# Ethernet.net
KiCad netlist of a schematic drawn in Altium Designer
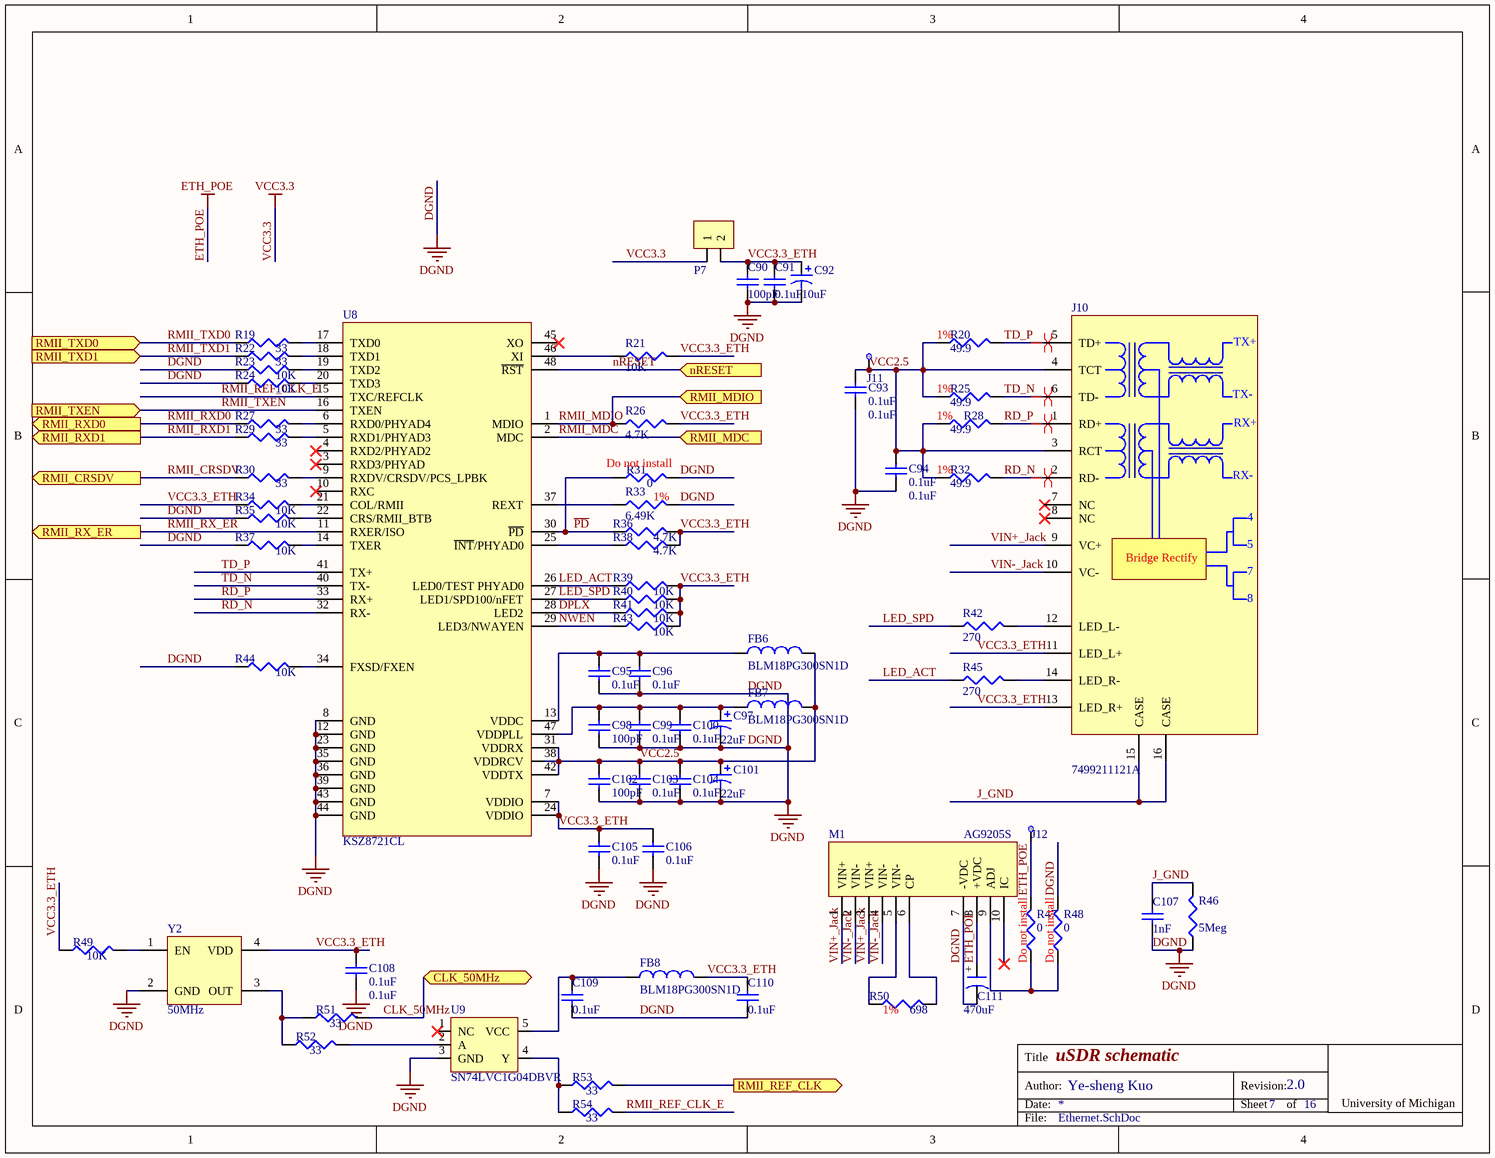
[diagram p0: Ethernet.SchDoc]

(export (version "E")
  (design (tool "Eeschema 10.0.6"))
  (components
    (comp (ref "C90")
      (value "100pF")
      (footprint "0402")
      (description "Capacitor (Semiconductor SIM Model)")
      (fields (field (name "PUBLISHER") "Altium Limited"))
      (libsource (lib "Miscellaneous Devices") (part "Cap Semi"))
    )
    (comp (ref "C91")
      (value "0.1uF")
      (footprint "0402")
      (description "Capacitor (Semiconductor SIM Model)")
      (fields (field (name "PUBLISHER") "Altium Limited"))
      (libsource (lib "Miscellaneous Devices") (part "Cap Semi"))
    )
    (comp (ref "C92")
      (value "10uF")
      (footprint "C0805")
      (description "Polarized Capacitor (Surface Mount)")
      (fields (field (name "PUBLISHER") "Altium Limited"))
      (libsource (lib "Miscellaneous Devices") (part "Cap Pol3"))
    )
    (comp (ref "C93")
      (value "0.1uF")
      (footprint "0402")
      (description "Capacitor (Semiconductor SIM Model)")
      (fields (field (name "ALTIUM_VALUE") "0.1uF") (field (name "PUBLISHER") "Altium Limited"))
      (libsource (lib "Miscellaneous Devices") (part "Cap Semi"))
    )
    (comp (ref "C94")
      (value "0.1uF")
      (footprint "0402")
      (description "Capacitor (Semiconductor SIM Model)")
      (fields (field (name "ALTIUM_VALUE") "0.1uF") (field (name "PUBLISHER") "Altium Limited"))
      (libsource (lib "Miscellaneous Devices") (part "Cap Semi"))
    )
    (comp (ref "C95")
      (value "0.1uF")
      (footprint "0402")
      (description "Capacitor (Semiconductor SIM Model)")
      (fields (field (name "PUBLISHER") "Altium Limited"))
      (libsource (lib "Miscellaneous Devices") (part "Cap Semi"))
    )
    (comp (ref "C96")
      (value "0.1uF")
      (footprint "0402")
      (description "Capacitor (Semiconductor SIM Model)")
      (fields (field (name "PUBLISHER") "Altium Limited"))
      (libsource (lib "Miscellaneous Devices") (part "Cap Semi"))
    )
    (comp (ref "C97")
      (value "22uF")
      (footprint "C0805")
      (description "Polarized Capacitor (Surface Mount)")
      (fields (field (name "PUBLISHER") "Altium Limited"))
      (libsource (lib "Miscellaneous Devices") (part "Cap Pol3"))
    )
    (comp (ref "C98")
      (value "100pF")
      (footprint "0402")
      (description "Capacitor (Semiconductor SIM Model)")
      (fields (field (name "PUBLISHER") "Altium Limited"))
      (libsource (lib "Miscellaneous Devices") (part "Cap Semi"))
    )
    (comp (ref "C99")
      (value "0.1uF")
      (footprint "0402")
      (description "Capacitor (Semiconductor SIM Model)")
      (fields (field (name "PUBLISHER") "Altium Limited"))
      (libsource (lib "Miscellaneous Devices") (part "Cap Semi"))
    )
    (comp (ref "C100")
      (value "0.1uF")
      (footprint "0402")
      (description "Capacitor (Semiconductor SIM Model)")
      (fields (field (name "PUBLISHER") "Altium Limited"))
      (libsource (lib "Miscellaneous Devices") (part "Cap Semi"))
    )
    (comp (ref "C101")
      (value "22uF")
      (footprint "C0805")
      (description "Polarized Capacitor (Surface Mount)")
      (fields (field (name "PUBLISHER") "Altium Limited"))
      (libsource (lib "Miscellaneous Devices") (part "Cap Pol3"))
    )
    (comp (ref "C102")
      (value "100pF")
      (footprint "0402")
      (description "Capacitor (Semiconductor SIM Model)")
      (fields (field (name "PUBLISHER") "Altium Limited"))
      (libsource (lib "Miscellaneous Devices") (part "Cap Semi"))
    )
    (comp (ref "C103")
      (value "0.1uF")
      (footprint "0402")
      (description "Capacitor (Semiconductor SIM Model)")
      (fields (field (name "PUBLISHER") "Altium Limited"))
      (libsource (lib "Miscellaneous Devices") (part "Cap Semi"))
    )
    (comp (ref "C104")
      (value "0.1uF")
      (footprint "0402")
      (description "Capacitor (Semiconductor SIM Model)")
      (fields (field (name "PUBLISHER") "Altium Limited"))
      (libsource (lib "Miscellaneous Devices") (part "Cap Semi"))
    )
    (comp (ref "C105")
      (value "0.1uF")
      (footprint "0402")
      (description "Capacitor (Semiconductor SIM Model)")
      (fields (field (name "PUBLISHER") "Altium Limited"))
      (libsource (lib "Miscellaneous Devices") (part "Cap Semi"))
    )
    (comp (ref "C106")
      (value "0.1uF")
      (footprint "0402")
      (description "Capacitor (Semiconductor SIM Model)")
      (fields (field (name "PUBLISHER") "Altium Limited"))
      (libsource (lib "Miscellaneous Devices") (part "Cap Semi"))
    )
    (comp (ref "C107")
      (value "1nF")
      (footprint "0402")
      (description "Capacitor (Semiconductor SIM Model)")
      (fields (field (name "PUBLISHER") "Altium Limited"))
      (libsource (lib "Miscellaneous Devices") (part "Cap Semi"))
    )
    (comp (ref "C108")
      (value "0.1uF")
      (footprint "0402")
      (description "Capacitor (Semiconductor SIM Model)")
      (fields (field (name "ALTIUM_VALUE") "0.1uF") (field (name "PUBLISHER") "Altium Limited"))
      (libsource (lib "Miscellaneous Devices") (part "Cap Semi"))
    )
    (comp (ref "C109")
      (value "0.1uF")
      (footprint "0402")
      (description "Capacitor (Semiconductor SIM Model)")
      (fields (field (name "PUBLISHER") "Altium Limited"))
      (libsource (lib "Miscellaneous Devices") (part "Cap Semi"))
    )
    (comp (ref "C110")
      (value "0.1uF")
      (footprint "0402")
      (description "Capacitor (Semiconductor SIM Model)")
      (fields (field (name "PUBLISHER") "Altium Limited"))
      (libsource (lib "Miscellaneous Devices") (part "Cap Semi"))
    )
    (comp (ref "C111") (value "470uF") (footprint "SMT Al Cap.") (libsource (lib "SDR") (part "Cap")))
    (comp (ref "FB6")
      (value "BLM18PG300SN1D")
      (footprint "1608[0603]")
      (description "FERRITE CHIP 30 OHM 1000MA 0603")
      (libsource (lib "SDR") (part "Ferrite Bead"))
    )
    (comp (ref "FB7")
      (value "BLM18PG300SN1D")
      (footprint "1608[0603]")
      (description "FERRITE CHIP 30 OHM 1000MA 0603")
      (libsource (lib "SDR") (part "Ferrite Bead"))
    )
    (comp (ref "FB8")
      (value "BLM18PG300SN1D")
      (footprint "1608[0603]")
      (description "FERRITE CHIP 30 OHM 1000MA 0603")
      (libsource (lib "SDR") (part "Ferrite Bead"))
    )
    (comp (ref "J10")
      (value "7499211121A")
      (footprint "7499211121A")
      (description "CONN RJ45 8-8 W/TRANSFORMER")
      (libsource (lib "SDR") (part "Ethernet Jack PoE"))
    )
    (comp (ref "J11")
      (value "5004")
      (footprint "TestPoint")
      (description "TEST POINT PC MINI .040\"D YELLOW")
      (libsource (lib "SDR") (part "TestPoint"))
    )
    (comp (ref "J12")
      (value "5004")
      (footprint "TestPoint")
      (description "TEST POINT PC MINI .040\"D YELLOW")
      (libsource (lib "SDR") (part "TestPoint"))
    )
    (comp (ref "M1")
      (value "AG9205S")
      (footprint "AG9205S")
      (description "Silver Telecom AG9205S POE")
      (libsource (lib "SDR") (part "AG9205S"))
    )
    (comp (ref "P7")
      (value "1 x 2 header")
      (footprint "1x2 header")
      (description "100 mils standard header")
      (libsource (lib "SDR") (part "1 x 2 header"))
    )
    (comp (ref "R19")
      (value "33")
      (footprint "0402")
      (description "Resistor")
      (fields (field (name "PUBLISHER") "Altium Limited"))
      (libsource (lib "Miscellaneous Devices") (part "Res3"))
    )
    (comp (ref "R20")
      (value "49.9")
      (footprint "0402")
      (description "Resistor")
      (fields (field (name "PUBLISHER") "Altium Limited"))
      (libsource (lib "Miscellaneous Devices") (part "Res3"))
    )
    (comp (ref "R21")
      (value "10K")
      (footprint "0402")
      (description "Resistor")
      (fields (field (name "PUBLISHER") "Altium Limited"))
      (libsource (lib "Miscellaneous Devices") (part "Res3"))
    )
    (comp (ref "R22")
      (value "33")
      (footprint "0402")
      (description "Resistor")
      (fields (field (name "PUBLISHER") "Altium Limited"))
      (libsource (lib "Miscellaneous Devices") (part "Res3"))
    )
    (comp (ref "R23")
      (value "10K")
      (footprint "0402")
      (description "Resistor")
      (fields (field (name "PUBLISHER") "Altium Limited"))
      (libsource (lib "Miscellaneous Devices") (part "Res3"))
    )
    (comp (ref "R24")
      (value "10K")
      (footprint "0402")
      (description "Resistor")
      (fields (field (name "PUBLISHER") "Altium Limited"))
      (libsource (lib "Miscellaneous Devices") (part "Res3"))
    )
    (comp (ref "R25")
      (value "49.9")
      (footprint "0402")
      (description "Resistor")
      (fields (field (name "PUBLISHER") "Altium Limited"))
      (libsource (lib "Miscellaneous Devices") (part "Res3"))
    )
    (comp (ref "R26")
      (value "4.7K")
      (footprint "0402")
      (description "Resistor")
      (fields (field (name "PUBLISHER") "Altium Limited"))
      (libsource (lib "Miscellaneous Devices") (part "Res3"))
    )
    (comp (ref "R27")
      (value "33")
      (footprint "0402")
      (description "Resistor")
      (fields (field (name "PUBLISHER") "Altium Limited"))
      (libsource (lib "Miscellaneous Devices") (part "Res3"))
    )
    (comp (ref "R28")
      (value "49.9")
      (footprint "0402")
      (description "Resistor")
      (fields (field (name "PUBLISHER") "Altium Limited"))
      (libsource (lib "Miscellaneous Devices") (part "Res3"))
    )
    (comp (ref "R29")
      (value "33")
      (footprint "0402")
      (description "Resistor")
      (fields (field (name "PUBLISHER") "Altium Limited"))
      (libsource (lib "Miscellaneous Devices") (part "Res3"))
    )
    (comp (ref "R30")
      (value "33")
      (footprint "0402")
      (description "Resistor")
      (fields (field (name "PUBLISHER") "Altium Limited"))
      (libsource (lib "Miscellaneous Devices") (part "Res3"))
    )
    (comp (ref "R31")
      (value "0")
      (footprint "0402")
      (description "Resistor")
      (fields (field (name "PUBLISHER") "Altium Limited"))
      (libsource (lib "Miscellaneous Devices") (part "Res3"))
    )
    (comp (ref "R32")
      (value "49.9")
      (footprint "0402")
      (description "Resistor")
      (fields (field (name "PUBLISHER") "Altium Limited"))
      (libsource (lib "Miscellaneous Devices") (part "Res3"))
    )
    (comp (ref "R33")
      (value "6.49K")
      (footprint "0402")
      (description "Resistor")
      (fields (field (name "PUBLISHER") "Altium Limited"))
      (libsource (lib "Miscellaneous Devices") (part "Res3"))
    )
    (comp (ref "R34")
      (value "10K")
      (footprint "0402")
      (description "Resistor")
      (fields (field (name "PUBLISHER") "Altium Limited"))
      (libsource (lib "Miscellaneous Devices") (part "Res3"))
    )
    (comp (ref "R35")
      (value "10K")
      (footprint "0402")
      (description "Resistor")
      (fields (field (name "PUBLISHER") "Altium Limited"))
      (libsource (lib "Miscellaneous Devices") (part "Res3"))
    )
    (comp (ref "R36")
      (value "4.7K")
      (footprint "0402")
      (description "Resistor")
      (fields (field (name "PUBLISHER") "Altium Limited"))
      (libsource (lib "Miscellaneous Devices") (part "Res3"))
    )
    (comp (ref "R37")
      (value "10K")
      (footprint "0402")
      (description "Resistor")
      (fields (field (name "PUBLISHER") "Altium Limited"))
      (libsource (lib "Miscellaneous Devices") (part "Res3"))
    )
    (comp (ref "R38")
      (value "4.7K")
      (footprint "0402")
      (description "Resistor")
      (fields (field (name "PUBLISHER") "Altium Limited"))
      (libsource (lib "Miscellaneous Devices") (part "Res3"))
    )
    (comp (ref "R39")
      (value "10K")
      (footprint "0402")
      (description "Resistor")
      (fields (field (name "PUBLISHER") "Altium Limited"))
      (libsource (lib "Miscellaneous Devices") (part "Res3"))
    )
    (comp (ref "R40")
      (value "10K")
      (footprint "0402")
      (description "Resistor")
      (fields (field (name "PUBLISHER") "Altium Limited"))
      (libsource (lib "Miscellaneous Devices") (part "Res3"))
    )
    (comp (ref "R41")
      (value "10K")
      (footprint "0402")
      (description "Resistor")
      (fields (field (name "PUBLISHER") "Altium Limited"))
      (libsource (lib "Miscellaneous Devices") (part "Res3"))
    )
    (comp (ref "R42")
      (value "270")
      (footprint "0402")
      (description "Resistor")
      (fields (field (name "PUBLISHER") "Altium Limited"))
      (libsource (lib "Miscellaneous Devices") (part "Res3"))
    )
    (comp (ref "R43")
      (value "10K")
      (footprint "0402")
      (description "Resistor")
      (fields (field (name "PUBLISHER") "Altium Limited"))
      (libsource (lib "Miscellaneous Devices") (part "Res3"))
    )
    (comp (ref "R44")
      (value "10K")
      (footprint "0402")
      (description "Resistor")
      (fields (field (name "PUBLISHER") "Altium Limited"))
      (libsource (lib "Miscellaneous Devices") (part "Res3"))
    )
    (comp (ref "R45")
      (value "270")
      (footprint "0402")
      (description "Resistor")
      (fields (field (name "PUBLISHER") "Altium Limited"))
      (libsource (lib "Miscellaneous Devices") (part "Res3"))
    )
    (comp (ref "R46")
      (value "5Meg")
      (footprint "J1-0603")
      (description "Resistor")
      (fields (field (name "Comment") "5M") (field (name "PUBLISHER") "Altium Limited"))
      (libsource (lib "Miscellaneous Devices") (part "Res3"))
    )
    (comp (ref "R47")
      (value "0")
      (footprint "0402")
      (description "Resistor")
      (fields (field (name "PUBLISHER") "Altium Limited"))
      (libsource (lib "Miscellaneous Devices") (part "Res3"))
    )
    (comp (ref "R48")
      (value "0")
      (footprint "0402")
      (description "Resistor")
      (fields (field (name "PUBLISHER") "Altium Limited"))
      (libsource (lib "Miscellaneous Devices") (part "Res3"))
    )
    (comp (ref "R49")
      (value "10K")
      (footprint "0402")
      (description "Resistor")
      (fields (field (name "PUBLISHER") "Altium Limited"))
      (libsource (lib "Miscellaneous Devices") (part "Res3"))
    )
    (comp (ref "R50")
      (value "698")
      (footprint "0402")
      (description "Resistor")
      (fields (field (name "PUBLISHER") "Altium Limited"))
      (libsource (lib "Miscellaneous Devices") (part "Res3"))
    )
    (comp (ref "R51")
      (value "33")
      (footprint "0402")
      (description "Resistor")
      (fields (field (name "PUBLISHER") "Altium Limited"))
      (libsource (lib "Miscellaneous Devices") (part "Res3"))
    )
    (comp (ref "R52")
      (value "33")
      (footprint "0402")
      (description "Resistor")
      (fields (field (name "PUBLISHER") "Altium Limited"))
      (libsource (lib "Miscellaneous Devices") (part "Res3"))
    )
    (comp (ref "R53")
      (value "33")
      (footprint "0402")
      (description "Resistor")
      (fields (field (name "PUBLISHER") "Altium Limited"))
      (libsource (lib "Miscellaneous Devices") (part "Res3"))
    )
    (comp (ref "R54")
      (value "33")
      (footprint "0402")
      (description "Resistor")
      (fields (field (name "PUBLISHER") "Altium Limited"))
      (libsource (lib "Miscellaneous Devices") (part "Res3"))
    )
    (comp (ref "U8")
      (value "KSZ8721CL")
      (footprint "TSQFP50P900X900X160-48N")
      (description "IC TXRX PHY 10/100 3.3V 48-LQFP")
      (libsource (lib "SDR") (part "KSZ8721CL"))
    )
    (comp (ref "U9")
      (value "SN74LVC1G04DBVR")
      (footprint "SOT23-5")
      (description "IC SINGLE INVERTER-GATE SOT-23-5")
      (libsource (lib "SDR") (part "SN74LVC1G04DBV"))
    )
    (comp (ref "Y2")
      (value "50MHz")
      (footprint "CB3_CB3LV")
      (description "OSC 50.000 MHZ 3.3V SMD")
      (fields (field (name "Comment") "CB3LV-3C-50M0000"))
      (libsource (lib "SDR") (part "CB3_CB3LV"))
    )
  )
  (nets
    (net (code "1") (name "/CLK_50MHz") (class "Default")
      (node (ref "R51") (pin "2") (pinfunction "2_2") (pintype "passive"))
    )
    (net (code "2") (name "/DPLX") (class "Default")
      (node (ref "R41") (pin "1") (pinfunction "1_1") (pintype "passive"))
      (node (ref "U8") (pin "28") (pinfunction "LED2_28") (pintype "passive"))
    )
    (net (code "3") (name "/J_GND") (class "Default")
      (node (ref "C107") (pin "2") (pinfunction "2_2") (pintype "passive"))
      (node (ref "J10") (pin "15") (pinfunction "CASE_15") (pintype "passive"))
      (node (ref "J10") (pin "16") (pinfunction "CASE_16") (pintype "passive"))
      (node (ref "R46") (pin "2") (pinfunction "2_2") (pintype "passive"))
    )
    (net (code "4") (name "/LED_ACT") (class "Default")
      (node (ref "R39") (pin "1") (pinfunction "1_1") (pintype "passive"))
      (node (ref "R45") (pin "1") (pinfunction "1_1") (pintype "passive"))
      (node (ref "U8") (pin "26") (pinfunction "LED0/TEST_PHYAD0_26") (pintype "passive"))
    )
    (net (code "5") (name "/LED_SPD") (class "Default")
      (node (ref "R40") (pin "1") (pinfunction "1_1") (pintype "passive"))
      (node (ref "R42") (pin "1") (pinfunction "1_1") (pintype "passive"))
      (node (ref "U8") (pin "27") (pinfunction "LED1/SPD100/nFET_27") (pintype "passive"))
    )
    (net (code "6") (name "/NWEN") (class "Default")
      (node (ref "R43") (pin "1") (pinfunction "1_1") (pintype "passive"))
      (node (ref "U8") (pin "29") (pinfunction "LED3/NWAYEN_29") (pintype "passive"))
    )
    (net (code "7") (name "/RD_N") (class "Default")
      (node (ref "J10") (pin "2") (pinfunction "RD-_2") (pintype "passive"))
      (node (ref "R32") (pin "2") (pinfunction "2_2") (pintype "passive"))
      (node (ref "U8") (pin "32") (pinfunction "RX-_32") (pintype "passive"))
    )
    (net (code "8") (name "/RD_P") (class "Default")
      (node (ref "J10") (pin "1") (pinfunction "RD+_1") (pintype "passive"))
      (node (ref "R28") (pin "2") (pinfunction "2_2") (pintype "passive"))
      (node (ref "U8") (pin "33") (pinfunction "RX+_33") (pintype "passive"))
    )
    (net (code "9") (name "/RMII_CRSDV") (class "Default")
      (node (ref "R30") (pin "1") (pinfunction "1_1") (pintype "passive"))
    )
    (net (code "10") (name "/RMII_MDC") (class "Default")
      (node (ref "U8") (pin "2") (pinfunction "MDC_2") (pintype "passive"))
    )
    (net (code "11") (name "/RMII_MDIO") (class "Default")
      (node (ref "R26") (pin "1") (pinfunction "1_1") (pintype "passive"))
      (node (ref "U8") (pin "1") (pinfunction "MDIO_1") (pintype "passive"))
    )
    (net (code "12") (name "/RMII_REF_CLK") (class "Default")
      (node (ref "R53") (pin "2") (pinfunction "2_2") (pintype "passive"))
    )
    (net (code "13") (name "/RMII_REF_CLK_E") (class "Default")
      (node (ref "R54") (pin "2") (pinfunction "2_2") (pintype "passive"))
      (node (ref "U8") (pin "15") (pinfunction "TXC/REFCLK_15") (pintype "passive"))
    )
    (net (code "14") (name "/RMII_RXD0") (class "Default")
      (node (ref "R27") (pin "1") (pinfunction "1_1") (pintype "passive"))
    )
    (net (code "15") (name "/RMII_RXD1") (class "Default")
      (node (ref "R29") (pin "1") (pinfunction "1_1") (pintype "passive"))
    )
    (net (code "16") (name "/RMII_RX_ER") (class "Default")
      (node (ref "U8") (pin "11") (pinfunction "RXER/ISO_11") (pintype "passive"))
    )
    (net (code "17") (name "/RMII_TXD0") (class "Default")
      (node (ref "R19") (pin "1") (pinfunction "1_1") (pintype "passive"))
    )
    (net (code "18") (name "/RMII_TXD1") (class "Default")
      (node (ref "R22") (pin "1") (pinfunction "1_1") (pintype "passive"))
    )
    (net (code "19") (name "/RMII_TXEN") (class "Default")
      (node (ref "U8") (pin "16") (pinfunction "TXEN_16") (pintype "passive"))
    )
    (net (code "20") (name "/TD_N") (class "Default")
      (node (ref "J10") (pin "6") (pinfunction "TD-_6") (pintype "passive"))
      (node (ref "R25") (pin "2") (pinfunction "2_2") (pintype "passive"))
      (node (ref "U8") (pin "40") (pinfunction "TX-_40") (pintype "passive"))
    )
    (net (code "21") (name "/TD_P") (class "Default")
      (node (ref "J10") (pin "5") (pinfunction "TD+_5") (pintype "passive"))
      (node (ref "R20") (pin "2") (pinfunction "2_2") (pintype "passive"))
      (node (ref "U8") (pin "41") (pinfunction "TX+_41") (pintype "passive"))
    )
    (net (code "22") (name "/VCC2.5") (class "Default")
      (node (ref "C101") (pin "1") (pinfunction "1_1") (pintype "passive"))
      (node (ref "C102") (pin "2") (pinfunction "2_2") (pintype "passive"))
      (node (ref "C103") (pin "2") (pinfunction "2_2") (pintype "passive"))
      (node (ref "C104") (pin "2") (pinfunction "2_2") (pintype "passive"))
      (node (ref "C93") (pin "2") (pinfunction "2_2") (pintype "passive"))
      (node (ref "C94") (pin "2") (pinfunction "2_2") (pintype "passive"))
      (node (ref "FB6") (pin "2") (pinfunction "2_2") (pintype "passive"))
      (node (ref "FB7") (pin "2") (pinfunction "2_2") (pintype "passive"))
      (node (ref "J10") (pin "3") (pinfunction "RCT_3") (pintype "passive"))
      (node (ref "J10") (pin "4") (pinfunction "TCT_4") (pintype "passive"))
      (node (ref "J11") (pin "1") (pinfunction "TB_1") (pintype "passive"))
      (node (ref "R20") (pin "1") (pinfunction "1_1") (pintype "passive"))
      (node (ref "R25") (pin "1") (pinfunction "1_1") (pintype "passive"))
      (node (ref "R28") (pin "1") (pinfunction "1_1") (pintype "passive"))
      (node (ref "R32") (pin "1") (pinfunction "1_1") (pintype "passive"))
      (node (ref "U8") (pin "31") (pinfunction "VDDRX_31") (pintype "passive"))
      (node (ref "U8") (pin "38") (pinfunction "VDDRCV_38") (pintype "passive"))
      (node (ref "U8") (pin "42") (pinfunction "VDDTX_42") (pintype "passive"))
    )
    (net (code "23") (name "/VCC3.3_ETH") (class "Default")
      (node (ref "C105") (pin "2") (pinfunction "2_2") (pintype "passive"))
      (node (ref "C106") (pin "2") (pinfunction "2_2") (pintype "passive"))
      (node (ref "C108") (pin "2") (pinfunction "2_2") (pintype "passive"))
      (node (ref "C110") (pin "2") (pinfunction "2_2") (pintype "passive"))
      (node (ref "C90") (pin "2") (pinfunction "2_2") (pintype "passive"))
      (node (ref "C91") (pin "2") (pinfunction "2_2") (pintype "passive"))
      (node (ref "C92") (pin "1") (pinfunction "1_1") (pintype "passive"))
      (node (ref "FB8") (pin "2") (pinfunction "2_2") (pintype "passive"))
      (node (ref "J10") (pin "11") (pinfunction "LED_L+_11") (pintype "passive"))
      (node (ref "J10") (pin "13") (pinfunction "LED_R+_13") (pintype "passive"))
      (node (ref "P7") (pin "2") (pinfunction "2_2") (pintype "passive"))
      (node (ref "R21") (pin "2") (pinfunction "2_2") (pintype "passive"))
      (node (ref "R26") (pin "2") (pinfunction "2_2") (pintype "passive"))
      (node (ref "R34") (pin "1") (pinfunction "1_1") (pintype "passive"))
      (node (ref "R36") (pin "2") (pinfunction "2_2") (pintype "passive"))
      (node (ref "R38") (pin "2") (pinfunction "2_2") (pintype "passive"))
      (node (ref "R39") (pin "2") (pinfunction "2_2") (pintype "passive"))
      (node (ref "R40") (pin "2") (pinfunction "2_2") (pintype "passive"))
      (node (ref "R41") (pin "2") (pinfunction "2_2") (pintype "passive"))
      (node (ref "R43") (pin "2") (pinfunction "2_2") (pintype "passive"))
      (node (ref "R49") (pin "1") (pinfunction "1_1") (pintype "passive"))
      (node (ref "U8") (pin "24") (pinfunction "VDDIO_24") (pintype "passive"))
      (node (ref "U8") (pin "7") (pinfunction "VDDIO_7") (pintype "passive"))
      (node (ref "Y2") (pin "4") (pinfunction "VDD_4") (pintype "passive"))
    )
    (net (code "24") (name "/VIN+_Jack") (class "Default")
      (node (ref "J10") (pin "9") (pinfunction "VC+_9") (pintype "passive"))
      (node (ref "M1") (pin "1") (pinfunction "VIN+_1") (pintype "passive"))
      (node (ref "M1") (pin "3") (pinfunction "VIN+_3") (pintype "passive"))
    )
    (net (code "25") (name "/VIN-_Jack") (class "Default")
      (node (ref "J10") (pin "10") (pinfunction "VC-_10") (pintype "passive"))
      (node (ref "M1") (pin "2") (pinfunction "VIN-_2") (pintype "passive"))
      (node (ref "M1") (pin "4") (pinfunction "VIN-_4") (pintype "passive"))
    )
    (net (code "26") (name "/nRESET") (class "Default")
      (node (ref "U8") (pin "48") (pinfunction "~{RST}_48") (pintype "passive"))
    )
    (net (code "27") (name "/~{PD}") (class "Default")
      (node (ref "R31") (pin "1") (pinfunction "1_1") (pintype "passive"))
      (node (ref "R36") (pin "1") (pinfunction "1_1") (pintype "passive"))
      (node (ref "U8") (pin "30") (pinfunction "~{PD}_30") (pintype "passive"))
    )
    (net (code "28") (name "DGND") (class "Default")
      (node (ref "C100") (pin "1") (pinfunction "1_1") (pintype "passive"))
      (node (ref "C101") (pin "2") (pinfunction "2_2") (pintype "passive"))
      (node (ref "C102") (pin "1") (pinfunction "1_1") (pintype "passive"))
      (node (ref "C103") (pin "1") (pinfunction "1_1") (pintype "passive"))
      (node (ref "C104") (pin "1") (pinfunction "1_1") (pintype "passive"))
      (node (ref "C105") (pin "1") (pinfunction "1_1") (pintype "passive"))
      (node (ref "C106") (pin "1") (pinfunction "1_1") (pintype "passive"))
      (node (ref "C107") (pin "1") (pinfunction "1_1") (pintype "passive"))
      (node (ref "C108") (pin "1") (pinfunction "1_1") (pintype "passive"))
      (node (ref "C109") (pin "1") (pinfunction "1_1") (pintype "passive"))
      (node (ref "C110") (pin "1") (pinfunction "1_1") (pintype "passive"))
      (node (ref "C111") (pin "-") (pintype "passive"))
      (node (ref "C90") (pin "1") (pinfunction "1_1") (pintype "passive"))
      (node (ref "C91") (pin "1") (pinfunction "1_1") (pintype "passive"))
      (node (ref "C92") (pin "2") (pinfunction "2_2") (pintype "passive"))
      (node (ref "C93") (pin "1") (pinfunction "1_1") (pintype "passive"))
      (node (ref "C94") (pin "1") (pinfunction "1_1") (pintype "passive"))
      (node (ref "C95") (pin "1") (pinfunction "1_1") (pintype "passive"))
      (node (ref "C96") (pin "1") (pinfunction "1_1") (pintype "passive"))
      (node (ref "C97") (pin "2") (pinfunction "2_2") (pintype "passive"))
      (node (ref "C98") (pin "1") (pinfunction "1_1") (pintype "passive"))
      (node (ref "C99") (pin "1") (pinfunction "1_1") (pintype "passive"))
      (node (ref "M1") (pin "7") (pinfunction "-VDC_7") (pintype "passive"))
      (node (ref "R23") (pin "1") (pinfunction "1_1") (pintype "passive"))
      (node (ref "R24") (pin "1") (pinfunction "1_1") (pintype "passive"))
      (node (ref "R31") (pin "2") (pinfunction "2_2") (pintype "passive"))
      (node (ref "R33") (pin "2") (pinfunction "2_2") (pintype "passive"))
      (node (ref "R35") (pin "1") (pinfunction "1_1") (pintype "passive"))
      (node (ref "R37") (pin "1") (pinfunction "1_1") (pintype "passive"))
      (node (ref "R44") (pin "1") (pinfunction "1_1") (pintype "passive"))
      (node (ref "R46") (pin "1") (pinfunction "1_1") (pintype "passive"))
      (node (ref "R48") (pin "2") (pinfunction "2_2") (pintype "passive"))
      (node (ref "U8") (pin "12") (pinfunction "GND_12") (pintype "passive"))
      (node (ref "U8") (pin "23") (pinfunction "GND_23") (pintype "passive"))
      (node (ref "U8") (pin "35") (pinfunction "GND_35") (pintype "passive"))
      (node (ref "U8") (pin "36") (pinfunction "GND_36") (pintype "passive"))
      (node (ref "U8") (pin "39") (pinfunction "GND_39") (pintype "passive"))
      (node (ref "U8") (pin "43") (pinfunction "GND_43") (pintype "passive"))
      (node (ref "U8") (pin "44") (pinfunction "GND_44") (pintype "passive"))
      (node (ref "U8") (pin "8") (pinfunction "GND_8") (pintype "passive"))
      (node (ref "U9") (pin "3") (pinfunction "GND_3") (pintype "passive"))
      (node (ref "Y2") (pin "2") (pinfunction "GND_2") (pintype "passive"))
    )
    (net (code "29") (name "ETH_POE") (class "Default")
      (node (ref "C111") (pin "+") (pinfunction "+_+") (pintype "passive"))
      (node (ref "J12") (pin "1") (pinfunction "TB_1") (pintype "passive"))
      (node (ref "M1") (pin "8") (pinfunction "+VDC_8") (pintype "passive"))
      (node (ref "R47") (pin "2") (pinfunction "2_2") (pintype "passive"))
    )
    (net (code "30") (name "Net-(J10-LED_L-)") (class "Default")
      (node (ref "J10") (pin "12") (pinfunction "LED_L-_12") (pintype "passive"))
      (node (ref "R42") (pin "2") (pinfunction "2_2") (pintype "passive"))
    )
    (net (code "31") (name "Net-(J10-LED_R-)") (class "Default")
      (node (ref "J10") (pin "14") (pinfunction "LED_R-_14") (pintype "passive"))
      (node (ref "R45") (pin "2") (pinfunction "2_2") (pintype "passive"))
    )
    (net (code "32") (name "Net-(M1-ADJ)") (class "Default")
      (node (ref "M1") (pin "9") (pinfunction "ADJ_9") (pintype "passive"))
      (node (ref "R47") (pin "1") (pinfunction "1_1") (pintype "passive"))
      (node (ref "R48") (pin "1") (pinfunction "1_1") (pintype "passive"))
    )
    (net (code "33") (name "Net-(M1-CP)") (class "Default")
      (node (ref "M1") (pin "6") (pinfunction "CP_6") (pintype "passive"))
      (node (ref "R50") (pin "2") (pinfunction "2_2") (pintype "passive"))
    )
    (net (code "34") (name "Net-(M1-VIN--Pad5)") (class "Default")
      (node (ref "M1") (pin "5") (pinfunction "VIN-_5") (pintype "passive"))
      (node (ref "R50") (pin "1") (pinfunction "1_1") (pintype "passive"))
    )
    (net (code "35") (name "Net-(U8-COL{slash}RMII)") (class "Default")
      (node (ref "R34") (pin "2") (pinfunction "2_2") (pintype "passive"))
      (node (ref "U8") (pin "21") (pinfunction "COL/RMII_21") (pintype "passive"))
    )
    (net (code "36") (name "Net-(U8-CRS{slash}RMII_BTB)") (class "Default")
      (node (ref "R35") (pin "2") (pinfunction "2_2") (pintype "passive"))
      (node (ref "U8") (pin "22") (pinfunction "CRS/RMII_BTB_22") (pintype "passive"))
    )
    (net (code "37") (name "Net-(U8-FXSD{slash}FXEN)") (class "Default")
      (node (ref "R44") (pin "2") (pinfunction "2_2") (pintype "passive"))
      (node (ref "U8") (pin "34") (pinfunction "FXSD/FXEN_34") (pintype "passive"))
    )
    (net (code "38") (name "Net-(U8-REXT)") (class "Default")
      (node (ref "R33") (pin "1") (pinfunction "1_1") (pintype "passive"))
      (node (ref "U8") (pin "37") (pinfunction "REXT_37") (pintype "passive"))
    )
    (net (code "39") (name "Net-(U8-RXD0{slash}PHYAD4)") (class "Default")
      (node (ref "R27") (pin "2") (pinfunction "2_2") (pintype "passive"))
      (node (ref "U8") (pin "6") (pinfunction "RXD0/PHYAD4_6") (pintype "passive"))
    )
    (net (code "40") (name "Net-(U8-RXD1{slash}PHYAD3)") (class "Default")
      (node (ref "R29") (pin "2") (pinfunction "2_2") (pintype "passive"))
      (node (ref "U8") (pin "5") (pinfunction "RXD1/PHYAD3_5") (pintype "passive"))
    )
    (net (code "41") (name "Net-(U8-RXDV{slash}CRSDV{slash}PCS_LPBK)") (class "Default")
      (node (ref "R30") (pin "2") (pinfunction "2_2") (pintype "passive"))
      (node (ref "U8") (pin "9") (pinfunction "RXDV/CRSDV/PCS_LPBK_9") (pintype "passive"))
    )
    (net (code "42") (name "Net-(U8-TXD0)") (class "Default")
      (node (ref "R19") (pin "2") (pinfunction "2_2") (pintype "passive"))
      (node (ref "U8") (pin "17") (pinfunction "TXD0_17") (pintype "passive"))
    )
    (net (code "43") (name "Net-(U8-TXD1)") (class "Default")
      (node (ref "R22") (pin "2") (pinfunction "2_2") (pintype "passive"))
      (node (ref "U8") (pin "18") (pinfunction "TXD1_18") (pintype "passive"))
    )
    (net (code "44") (name "Net-(U8-TXD2)") (class "Default")
      (node (ref "R23") (pin "2") (pinfunction "2_2") (pintype "passive"))
      (node (ref "U8") (pin "19") (pinfunction "TXD2_19") (pintype "passive"))
    )
    (net (code "45") (name "Net-(U8-TXD3)") (class "Default")
      (node (ref "R24") (pin "2") (pinfunction "2_2") (pintype "passive"))
      (node (ref "U8") (pin "20") (pinfunction "TXD3_20") (pintype "passive"))
    )
    (net (code "46") (name "Net-(U8-TXER)") (class "Default")
      (node (ref "R37") (pin "2") (pinfunction "2_2") (pintype "passive"))
      (node (ref "U8") (pin "14") (pinfunction "TXER_14") (pintype "passive"))
    )
    (net (code "47") (name "Net-(U8-VDDC)") (class "Default")
      (node (ref "C95") (pin "2") (pinfunction "2_2") (pintype "passive"))
      (node (ref "C96") (pin "2") (pinfunction "2_2") (pintype "passive"))
      (node (ref "FB6") (pin "1") (pinfunction "1_1") (pintype "passive"))
      (node (ref "U8") (pin "13") (pinfunction "VDDC_13") (pintype "passive"))
    )
    (net (code "48") (name "Net-(U8-VDDPLL)") (class "Default")
      (node (ref "C100") (pin "2") (pinfunction "2_2") (pintype "passive"))
      (node (ref "C97") (pin "1") (pinfunction "1_1") (pintype "passive"))
      (node (ref "C98") (pin "2") (pinfunction "2_2") (pintype "passive"))
      (node (ref "C99") (pin "2") (pinfunction "2_2") (pintype "passive"))
      (node (ref "FB7") (pin "1") (pinfunction "1_1") (pintype "passive"))
      (node (ref "U8") (pin "47") (pinfunction "VDDPLL_47") (pintype "passive"))
    )
    (net (code "49") (name "Net-(U8-XI)") (class "Default")
      (node (ref "R21") (pin "1") (pinfunction "1_1") (pintype "passive"))
      (node (ref "U8") (pin "46") (pinfunction "XI_46") (pintype "passive"))
    )
    (net (code "50") (name "Net-(U8-~{INT}{slash}PHYAD0)") (class "Default")
      (node (ref "R38") (pin "1") (pinfunction "1_1") (pintype "passive"))
      (node (ref "U8") (pin "25") (pinfunction "~{INT}/PHYAD0_25") (pintype "passive"))
    )
    (net (code "51") (name "Net-(U9-A)") (class "Default")
      (node (ref "R52") (pin "2") (pinfunction "2_2") (pintype "passive"))
      (node (ref "U9") (pin "2") (pinfunction "A_2") (pintype "passive"))
    )
    (net (code "52") (name "Net-(U9-VCC)") (class "Default")
      (node (ref "C109") (pin "2") (pinfunction "2_2") (pintype "passive"))
      (node (ref "FB8") (pin "1") (pinfunction "1_1") (pintype "passive"))
      (node (ref "U9") (pin "5") (pinfunction "VCC_5") (pintype "passive"))
    )
    (net (code "53") (name "Net-(U9-Y)") (class "Default")
      (node (ref "R53") (pin "1") (pinfunction "1_1") (pintype "passive"))
      (node (ref "R54") (pin "1") (pinfunction "1_1") (pintype "passive"))
      (node (ref "U9") (pin "4") (pinfunction "Y_4") (pintype "passive"))
    )
    (net (code "54") (name "Net-(Y2-EN)") (class "Default")
      (node (ref "R49") (pin "2") (pinfunction "2_2") (pintype "passive"))
      (node (ref "Y2") (pin "1") (pinfunction "EN_1") (pintype "passive"))
    )
    (net (code "55") (name "Net-(Y2-OUT)") (class "Default")
      (node (ref "R51") (pin "1") (pinfunction "1_1") (pintype "passive"))
      (node (ref "R52") (pin "1") (pinfunction "1_1") (pintype "passive"))
      (node (ref "Y2") (pin "3") (pinfunction "OUT_3") (pintype "passive"))
    )
    (net (code "56") (name "VCC3.3") (class "Default")
      (node (ref "P7") (pin "1") (pinfunction "1_1") (pintype "passive"))
    )
    (net (code "57") (name "unconnected-(J10-NC-Pad7)") (class "Default")
      (node (ref "J10") (pin "7") (pinfunction "NC_7") (pintype "passive+no_connect"))
    )
    (net (code "58") (name "unconnected-(J10-NC-Pad8)") (class "Default")
      (node (ref "J10") (pin "8") (pinfunction "NC_8") (pintype "passive+no_connect"))
    )
    (net (code "59") (name "unconnected-(M1-IC-Pad10)") (class "Default")
      (node (ref "M1") (pin "10") (pinfunction "IC_10") (pintype "passive+no_connect"))
    )
    (net (code "60") (name "unconnected-(U8-RXC-Pad10)") (class "Default")
      (node (ref "U8") (pin "10") (pinfunction "RXC_10") (pintype "passive+no_connect"))
    )
    (net (code "61") (name "unconnected-(U8-RXD2{slash}PHYAD2-Pad4)") (class "Default")
      (node (ref "U8") (pin "4") (pinfunction "RXD2/PHYAD2_4") (pintype "passive+no_connect"))
    )
    (net (code "62") (name "unconnected-(U8-RXD3{slash}PHYAD-Pad3)") (class "Default")
      (node (ref "U8") (pin "3") (pinfunction "RXD3/PHYAD_3") (pintype "passive+no_connect"))
    )
    (net (code "63") (name "unconnected-(U8-XO-Pad45)") (class "Default")
      (node (ref "U8") (pin "45") (pinfunction "XO_45") (pintype "passive+no_connect"))
    )
    (net (code "64") (name "unconnected-(U9-NC-Pad1)") (class "Default")
      (node (ref "U9") (pin "1") (pinfunction "NC_1") (pintype "passive+no_connect"))
    )
  )
)
